# spi_barometer.net
KiCad netlist of a schematic drawn in EAGLE
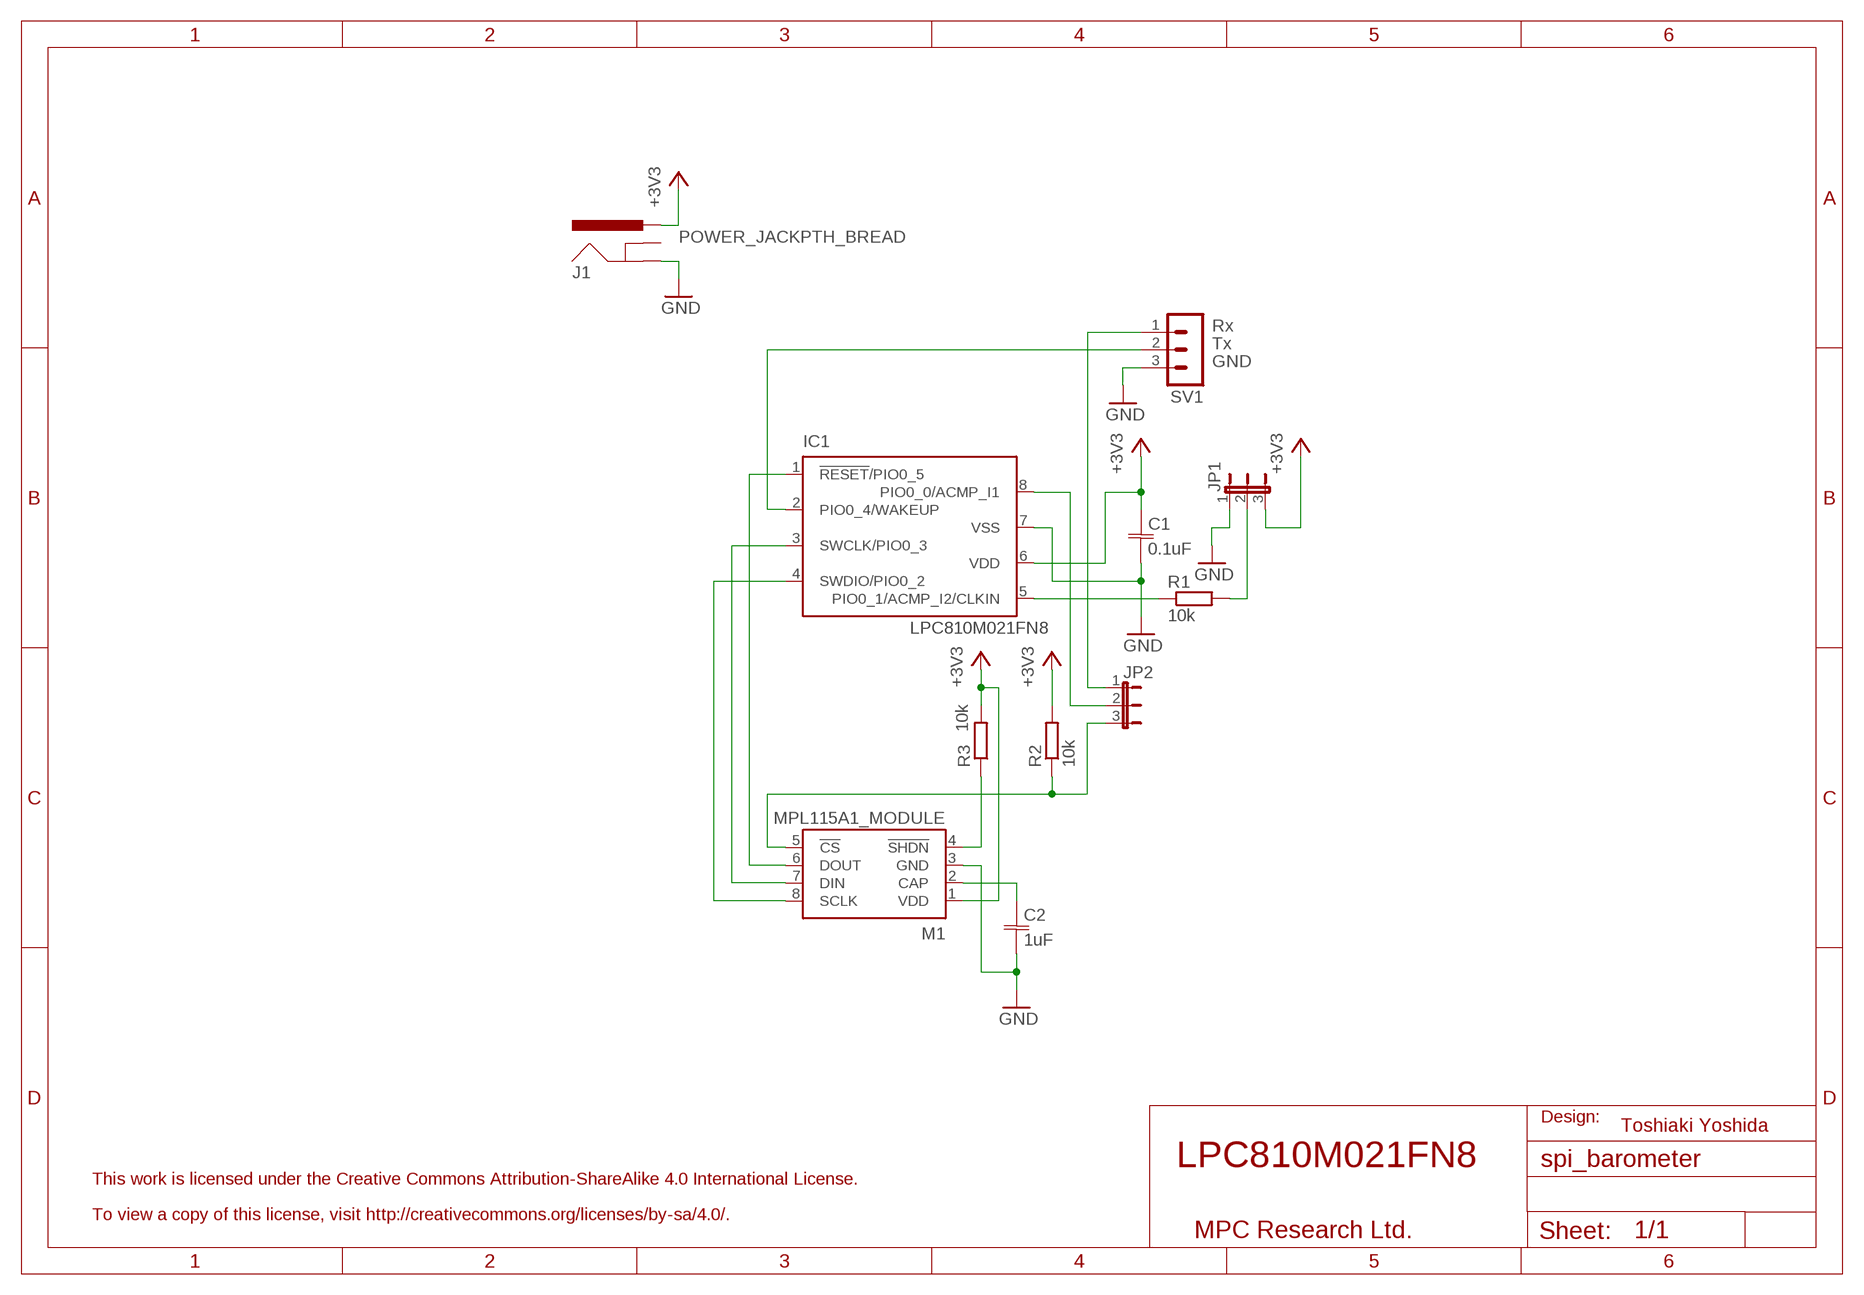
[diagram p0: schematic, sheet 1]

(export (version "E")
  (design (tool "Eeschema 10.0.6"))
  (components
    (comp (ref "C1")
      (value "0.1uF")
      (footprint "eagle-import:C050-024X044")
      (libsource (lib "eagle-import") (part "C-JIS050-024X044"))
    )
    (comp (ref "C2")
      (value "1uF")
      (footprint "eagle-import:C050-024X044")
      (libsource (lib "eagle-import") (part "C-JIS050-024X044"))
    )
    (comp (ref "IC1")
      (value "LPC810M021FN8")
      (footprint "eagle-import:DIL08")
      (libsource (lib "eagle-import") (part "LPC810M021FN8"))
    )
    (comp (ref "J1")
      (value "POWER_JACKPTH_BREAD")
      (footprint "eagle-import:POWER_JACK_PTH_BREAD")
      (libsource (lib "eagle-import") (part "POWER_JACKPTH_BREAD"))
    )
    (comp (ref "JP1")
      (value "JP2E")
      (footprint "eagle-import:JP2")
      (libsource (lib "eagle-import") (part "JP2E"))
    )
    (comp (ref "JP2")
      (value "JP2E")
      (footprint "eagle-import:JP2")
      (libsource (lib "eagle-import") (part "JP2E"))
    )
    (comp (ref "M1")
      (value "MPL115A1_MODULE")
      (footprint "eagle-import:DIL8")
      (libsource (lib "eagle-import") (part "MPL115A1_MODULE"))
    )
    (comp (ref "R1")
      (value "10k")
      (footprint "eagle-import:0207_10")
      (libsource (lib "eagle-import") (part "R-EU_0207/10"))
    )
    (comp (ref "R2")
      (value "10k")
      (footprint "eagle-import:0207_10")
      (libsource (lib "eagle-import") (part "R-EU_0207/10"))
    )
    (comp (ref "R3")
      (value "10k")
      (footprint "eagle-import:0207_10")
      (libsource (lib "eagle-import") (part "R-EU_0207/10"))
    )
    (comp (ref "SV1")
      (value "MA03-1")
      (footprint "eagle-import:MA03-1")
      (libsource (lib "eagle-import") (part "MA03-1"))
    )
  )
  (nets
    (net (code "1") (name "+3V3") (class "Default")
      (node (ref "C1") (pin "1") (pinfunction "1_1") (pintype "passive"))
      (node (ref "IC1") (pin "6") (pinfunction "VDD_6") (pintype "power_in"))
      (node (ref "J1") (pin "PWR") (pinfunction "PWR_PWR") (pintype "bidirectional"))
      (node (ref "JP1") (pin "3") (pinfunction "3_3") (pintype "passive"))
      (node (ref "M1") (pin "1") (pinfunction "VDD_1") (pintype "power_in"))
      (node (ref "R2") (pin "2") (pinfunction "2_2") (pintype "passive"))
      (node (ref "R3") (pin "2") (pinfunction "2_2") (pintype "passive"))
    )
    (net (code "2") (name "GND") (class "Default")
      (node (ref "C1") (pin "2") (pinfunction "2_2") (pintype "passive"))
      (node (ref "C2") (pin "2") (pinfunction "2_2") (pintype "passive"))
      (node (ref "IC1") (pin "7") (pinfunction "VSS_7") (pintype "power_in"))
      (node (ref "J1") (pin "GND") (pinfunction "GND_GND") (pintype "bidirectional"))
      (node (ref "JP1") (pin "1") (pinfunction "1_1") (pintype "passive"))
      (node (ref "M1") (pin "3") (pinfunction "GND_3") (pintype "power_in"))
      (node (ref "SV1") (pin "3") (pinfunction "3_3") (pintype "passive"))
    )
    (net (code "3") (name "Net-(IC1-PIO0_0{slash}ACMP_I1)") (class "Default")
      (node (ref "IC1") (pin "8") (pinfunction "PIO0_0/ACMP_I1_8") (pintype "bidirectional"))
      (node (ref "JP2") (pin "2") (pinfunction "2_2") (pintype "passive"))
    )
    (net (code "4") (name "Net-(IC1-PIO0_1{slash}ACMP_I2{slash}CLKIN)") (class "Default")
      (node (ref "IC1") (pin "5") (pinfunction "PIO0_1/ACMP_I2/CLKIN_5") (pintype "bidirectional"))
      (node (ref "R1") (pin "1") (pinfunction "1_1") (pintype "passive"))
    )
    (net (code "5") (name "Net-(IC1-PIO0_4{slash}WAKEUP)") (class "Default")
      (node (ref "IC1") (pin "2") (pinfunction "PIO0_4/WAKEUP_2") (pintype "bidirectional"))
      (node (ref "SV1") (pin "2") (pinfunction "2_2") (pintype "passive"))
    )
    (net (code "6") (name "Net-(IC1-SWCLK{slash}PIO0_3)") (class "Default")
      (node (ref "IC1") (pin "3") (pinfunction "SWCLK/PIO0_3_3") (pintype "bidirectional"))
      (node (ref "M1") (pin "7") (pinfunction "DIN_7") (pintype "input"))
    )
    (net (code "7") (name "Net-(IC1-SWDIO{slash}PIO0_2)") (class "Default")
      (node (ref "IC1") (pin "4") (pinfunction "SWDIO/PIO0_2_4") (pintype "bidirectional"))
      (node (ref "M1") (pin "8") (pinfunction "SCLK_8") (pintype "input"))
    )
    (net (code "8") (name "Net-(IC1-~{RESET}{slash}PIO0_5)") (class "Default")
      (node (ref "IC1") (pin "1") (pinfunction "~{RESET}/PIO0_5_1") (pintype "bidirectional"))
      (node (ref "M1") (pin "6") (pinfunction "DOUT_6") (pintype "output"))
    )
    (net (code "9") (name "Net-(JP1-Pad2)") (class "Default")
      (node (ref "JP1") (pin "2") (pinfunction "2_2") (pintype "passive"))
      (node (ref "R1") (pin "2") (pinfunction "2_2") (pintype "passive"))
    )
    (net (code "10") (name "Net-(JP2-Pad1)") (class "Default")
      (node (ref "JP2") (pin "1") (pinfunction "1_1") (pintype "passive"))
      (node (ref "SV1") (pin "1") (pinfunction "1_1") (pintype "passive"))
    )
    (net (code "11") (name "Net-(M1-CAP)") (class "Default")
      (node (ref "C2") (pin "1") (pinfunction "1_1") (pintype "passive"))
      (node (ref "M1") (pin "2") (pinfunction "CAP_2") (pintype "passive"))
    )
    (net (code "12") (name "Net-(M1-~{CS})") (class "Default")
      (node (ref "JP2") (pin "3") (pinfunction "3_3") (pintype "passive"))
      (node (ref "M1") (pin "5") (pinfunction "~{CS}_5") (pintype "input"))
      (node (ref "R2") (pin "1") (pinfunction "1_1") (pintype "passive"))
    )
    (net (code "13") (name "Net-(M1-~{SHDN})") (class "Default")
      (node (ref "M1") (pin "4") (pinfunction "~{SHDN}_4") (pintype "input"))
      (node (ref "R3") (pin "1") (pinfunction "1_1") (pintype "passive"))
    )
    (net (code "14") (name "unconnected-(J1-PadGNDBREAK)") (class "Default")
      (node (ref "J1") (pin "GNDBREAK") (pinfunction "GNDBREAK_GNDBREAK") (pintype "bidirectional"))
    )
  )
)
